# sch.net
KiCad netlist of a schematic drawn in EAGLE
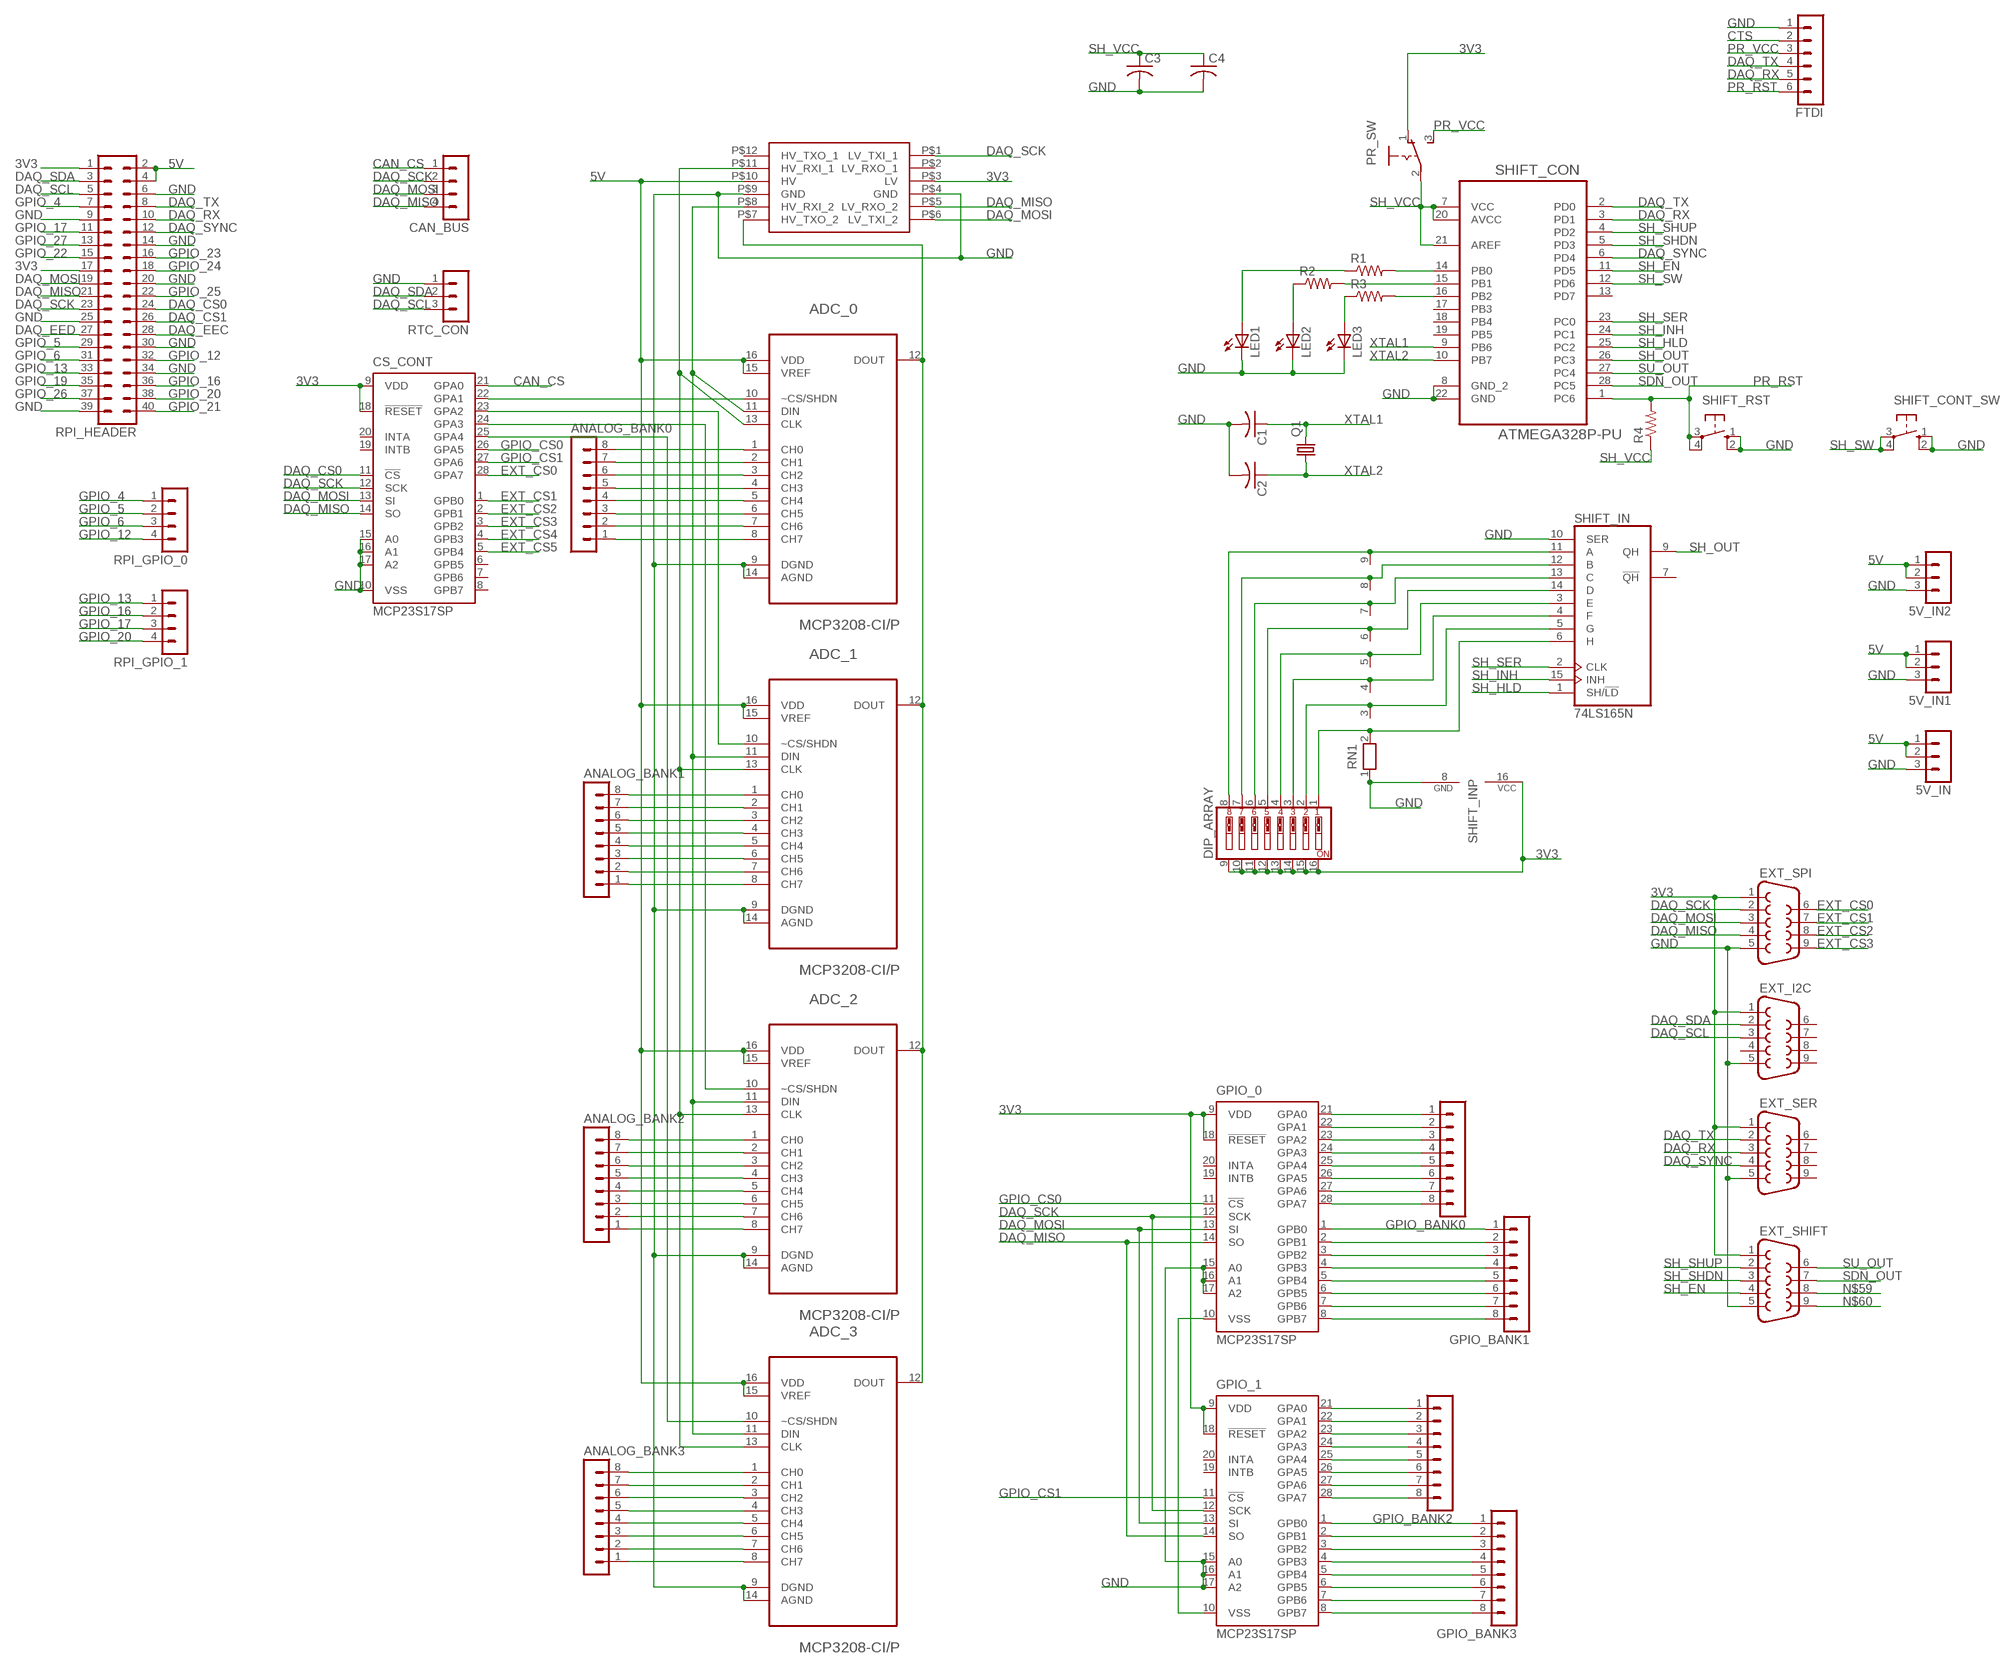
[diagram p0: schematic, sheet 1]

(export (version "E")
  (design (tool "Eeschema 10.0.6"))
  (components
    (comp (ref "5V_IN")
      (value "MA03-1")
      (footprint "eagle-import:MA03-1")
      (libsource (lib "eagle-import") (part "MA03-1"))
    )
    (comp (ref "5V_IN1")
      (value "MA03-1")
      (footprint "eagle-import:MA03-1")
      (libsource (lib "eagle-import") (part "MA03-1"))
    )
    (comp (ref "5V_IN2")
      (value "MA03-1")
      (footprint "eagle-import:MA03-1")
      (libsource (lib "eagle-import") (part "MA03-1"))
    )
    (comp (ref "ADC_0")
      (value "MCP3208-CI/P")
      (footprint "eagle-import:DIP254P762X432-16")
      (libsource (lib "eagle-import") (part "MCP3208-CI/P"))
    )
    (comp (ref "ADC_1")
      (value "MCP3208-CI/P")
      (footprint "eagle-import:DIP254P762X432-16")
      (libsource (lib "eagle-import") (part "MCP3208-CI/P"))
    )
    (comp (ref "ADC_2")
      (value "MCP3208-CI/P")
      (footprint "eagle-import:DIP254P762X432-16")
      (libsource (lib "eagle-import") (part "MCP3208-CI/P"))
    )
    (comp (ref "ADC_3")
      (value "MCP3208-CI/P")
      (footprint "eagle-import:DIP254P762X432-16")
      (libsource (lib "eagle-import") (part "MCP3208-CI/P"))
    )
    (comp (ref "ANALOG_BANK0")
      (value "MA08-1")
      (footprint "eagle-import:MA08-1")
      (libsource (lib "eagle-import") (part "MA08-1"))
    )
    (comp (ref "ANALOG_BANK1")
      (value "MA08-1")
      (footprint "eagle-import:MA08-1")
      (libsource (lib "eagle-import") (part "MA08-1"))
    )
    (comp (ref "ANALOG_BANK2")
      (value "MA08-1")
      (footprint "eagle-import:MA08-1")
      (libsource (lib "eagle-import") (part "MA08-1"))
    )
    (comp (ref "ANALOG_BANK3")
      (value "MA08-1")
      (footprint "eagle-import:MA08-1")
      (libsource (lib "eagle-import") (part "MA08-1"))
    )
    (comp (ref "C1")
      (value "C-US025-025X050")
      (footprint "eagle-import:C025-025X050")
      (libsource (lib "eagle-import") (part "C-US025-025X050"))
    )
    (comp (ref "C2")
      (value "C-US025-025X050")
      (footprint "eagle-import:C025-025X050")
      (libsource (lib "eagle-import") (part "C-US025-025X050"))
    )
    (comp (ref "C3")
      (value "C-US025-025X050")
      (footprint "eagle-import:C025-025X050")
      (libsource (lib "eagle-import") (part "C-US025-025X050"))
    )
    (comp (ref "C4")
      (value "C-US025-025X050")
      (footprint "eagle-import:C025-025X050")
      (libsource (lib "eagle-import") (part "C-US025-025X050"))
    )
    (comp (ref "CAN_BUS")
      (value "MA04-1")
      (footprint "eagle-import:MA04-1")
      (libsource (lib "eagle-import") (part "MA04-1"))
    )
    (comp (ref "CS_CONT")
      (value "MCP23S17SP")
      (footprint "eagle-import:DIL28-3")
      (fields (field (name "MF") "MICROCHIP") (field (name "MPN") "MCP23S17-E/SP"))
      (libsource (lib "eagle-import") (part "MCP23S17SP"))
    )
    (comp (ref "DIP_ARRAY")
      (value "SW_DIP-8")
      (footprint "eagle-import:DIPSWITCH-08")
      (libsource (lib "eagle-import") (part "SW_DIP-8"))
    )
    (comp (ref "EXT_I2C")
      (value "F09VB")
      (footprint "eagle-import:F09VB")
      (libsource (lib "eagle-import") (part "F09VB"))
    )
    (comp (ref "EXT_SER")
      (value "F09VB")
      (footprint "eagle-import:F09VB")
      (libsource (lib "eagle-import") (part "F09VB"))
    )
    (comp (ref "EXT_SHIFT")
      (value "F09VB")
      (footprint "eagle-import:F09VB")
      (libsource (lib "eagle-import") (part "F09VB"))
    )
    (comp (ref "EXT_SPI")
      (value "F09VB")
      (footprint "eagle-import:F09VB")
      (libsource (lib "eagle-import") (part "F09VB"))
    )
    (comp (ref "FTDI")
      (value "MA06-1")
      (footprint "eagle-import:MA06-1")
      (libsource (lib "eagle-import") (part "MA06-1"))
    )
    (comp (ref "GPIO_0")
      (value "MCP23S17SP")
      (footprint "eagle-import:DIL28-3")
      (fields (field (name "MF") "MICROCHIP") (field (name "MPN") "MCP23S17-E/SP"))
      (libsource (lib "eagle-import") (part "MCP23S17SP"))
    )
    (comp (ref "GPIO_1")
      (value "MCP23S17SP")
      (footprint "eagle-import:DIL28-3")
      (fields (field (name "MF") "MICROCHIP") (field (name "MPN") "MCP23S17-E/SP"))
      (libsource (lib "eagle-import") (part "MCP23S17SP"))
    )
    (comp (ref "GPIO_BANK0")
      (value "MA08-1")
      (footprint "eagle-import:MA08-1")
      (libsource (lib "eagle-import") (part "MA08-1"))
    )
    (comp (ref "GPIO_BANK1")
      (value "MA08-1")
      (footprint "eagle-import:MA08-1")
      (libsource (lib "eagle-import") (part "MA08-1"))
    )
    (comp (ref "GPIO_BANK2")
      (value "MA08-1")
      (footprint "eagle-import:MA08-1")
      (libsource (lib "eagle-import") (part "MA08-1"))
    )
    (comp (ref "GPIO_BANK3")
      (value "MA08-1")
      (footprint "eagle-import:MA08-1")
      (libsource (lib "eagle-import") (part "MA08-1"))
    )
    (comp (ref "LED1")
      (value "LED3MM")
      (footprint "eagle-import:LED3MM")
      (libsource (lib "eagle-import") (part "LED3MM"))
    )
    (comp (ref "LED2")
      (value "LED3MM")
      (footprint "eagle-import:LED3MM")
      (libsource (lib "eagle-import") (part "LED3MM"))
    )
    (comp (ref "LED3")
      (value "LED3MM")
      (footprint "eagle-import:LED3MM")
      (libsource (lib "eagle-import") (part "LED3MM"))
    )
    (comp (ref "LOGIC_SHIFT")
      (value "LOGIC_LEVEL_CONVERTER")
      (footprint "eagle-import:LOGIC_LEVEL_CONVERTER")
      (libsource (lib "eagle-import") (part "LOGIC_LEVEL_CONVERTER"))
    )
    (comp (ref "PR_SW")
      (value "255SB")
      (footprint "eagle-import:255SB")
      (libsource (lib "eagle-import") (part "255SB"))
    )
    (comp (ref "Q1")
      (value "CRYSTALHC49S")
      (footprint "eagle-import:HC49_S")
      (libsource (lib "eagle-import") (part "CRYSTALHC49S"))
    )
    (comp (ref "R1")
      (value "R-US_0204/5")
      (footprint "eagle-import:0204_5")
      (libsource (lib "eagle-import") (part "R-US_0204/5"))
    )
    (comp (ref "R2")
      (value "R-US_0204/5")
      (footprint "eagle-import:0204_5")
      (libsource (lib "eagle-import") (part "R-US_0204/5"))
    )
    (comp (ref "R3")
      (value "R-US_0204/5")
      (footprint "eagle-import:0204_5")
      (libsource (lib "eagle-import") (part "R-US_0204/5"))
    )
    (comp (ref "R4")
      (value "R-US_0204/5")
      (footprint "eagle-import:0204_5")
      (libsource (lib "eagle-import") (part "R-US_0204/5"))
    )
    (comp (ref "RN1")
      (value "RN08")
      (footprint "eagle-import:RN-9")
      (libsource (lib "eagle-import") (part "RN08"))
    )
    (comp (ref "RPI_GPIO_0")
      (value "MA04-1")
      (footprint "eagle-import:MA04-1")
      (libsource (lib "eagle-import") (part "MA04-1"))
    )
    (comp (ref "RPI_GPIO_1")
      (value "MA04-1")
      (footprint "eagle-import:MA04-1")
      (libsource (lib "eagle-import") (part "MA04-1"))
    )
    (comp (ref "RPI_HEADER")
      (value "MA20-2")
      (footprint "eagle-import:MA20-2")
      (libsource (lib "eagle-import") (part "MA20-2"))
    )
    (comp (ref "RTC_CON")
      (value "MA03-1")
      (footprint "eagle-import:MA03-1")
      (libsource (lib "eagle-import") (part "MA03-1"))
    )
    (comp (ref "SHIFT_CON")
      (value "ATMEGA328P-PU")
      (footprint "eagle-import:DIP254P762X457-28")
      (libsource (lib "eagle-import") (part "ATMEGA328P-PU"))
    )
    (comp (ref "SHIFT_CONT_SW")
      (value "10-XX")
      (footprint "eagle-import:B3F-10XX")
      (fields (field (name "MPN") "B3F-1000"))
      (libsource (lib "eagle-import") (part "10-XX"))
    )
    (comp (ref "SHIFT_IN")
      (value "74LS165N")
      (footprint "eagle-import:DIL16")
      (libsource (lib "eagle-import") (part "74165NLS"))
    )
    (comp (ref "SHIFT_RST")
      (value "10-XX")
      (footprint "eagle-import:B3F-10XX")
      (fields (field (name "MPN") "B3F-1000"))
      (libsource (lib "eagle-import") (part "10-XX"))
    )
  )
  (nets
    (net (code "1") (name "/3V3") (class "Default")
      (node (ref "CS_CONT") (pin "18") (pinfunction "~{RESET}_18") (pintype "input"))
      (node (ref "CS_CONT") (pin "9") (pinfunction "VDD_9") (pintype "power_in"))
      (node (ref "DIP_ARRAY") (pin "10") (pinfunction "10_10") (pintype "passive"))
      (node (ref "DIP_ARRAY") (pin "11") (pinfunction "11_11") (pintype "passive"))
      (node (ref "DIP_ARRAY") (pin "12") (pinfunction "12_12") (pintype "passive"))
      (node (ref "DIP_ARRAY") (pin "13") (pinfunction "13_13") (pintype "passive"))
      (node (ref "DIP_ARRAY") (pin "14") (pinfunction "14_14") (pintype "passive"))
      (node (ref "DIP_ARRAY") (pin "15") (pinfunction "15_15") (pintype "passive"))
      (node (ref "DIP_ARRAY") (pin "16") (pinfunction "16_16") (pintype "passive"))
      (node (ref "DIP_ARRAY") (pin "9") (pinfunction "9_9") (pintype "passive"))
      (node (ref "EXT_I2C") (pin "1") (pinfunction "1_1") (pintype "passive"))
      (node (ref "EXT_SER") (pin "1") (pinfunction "1_1") (pintype "passive"))
      (node (ref "EXT_SHIFT") (pin "1") (pinfunction "1_1") (pintype "passive"))
      (node (ref "EXT_SPI") (pin "1") (pinfunction "1_1") (pintype "passive"))
      (node (ref "GPIO_0") (pin "18") (pinfunction "~{RESET}_18") (pintype "input"))
      (node (ref "GPIO_0") (pin "9") (pinfunction "VDD_9") (pintype "power_in"))
      (node (ref "GPIO_1") (pin "18") (pinfunction "~{RESET}_18") (pintype "input"))
      (node (ref "GPIO_1") (pin "9") (pinfunction "VDD_9") (pintype "power_in"))
      (node (ref "LOGIC_SHIFT") (pin "P$3") (pinfunction "LV_P$3") (pintype "bidirectional"))
      (node (ref "PR_SW") (pin "1") (pinfunction "O_1") (pintype "passive"))
      (node (ref "RPI_HEADER") (pin "1") (pinfunction "1_1") (pintype "passive"))
      (node (ref "RPI_HEADER") (pin "17") (pinfunction "17_17") (pintype "passive"))
      (node (ref "SHIFT_IN") (pin "16") (pinfunction "VCC_16") (pintype "power_in"))
    )
    (net (code "2") (name "/5V") (class "Default")
      (node (ref "5V_IN") (pin "1") (pinfunction "1_1") (pintype "passive"))
      (node (ref "5V_IN") (pin "2") (pinfunction "2_2") (pintype "passive"))
      (node (ref "5V_IN1") (pin "1") (pinfunction "1_1") (pintype "passive"))
      (node (ref "5V_IN1") (pin "2") (pinfunction "2_2") (pintype "passive"))
      (node (ref "5V_IN2") (pin "1") (pinfunction "1_1") (pintype "passive"))
      (node (ref "5V_IN2") (pin "2") (pinfunction "2_2") (pintype "passive"))
      (node (ref "ADC_0") (pin "15") (pinfunction "VREF_15") (pintype "power_in"))
      (node (ref "ADC_0") (pin "16") (pinfunction "VDD_16") (pintype "power_in"))
      (node (ref "ADC_1") (pin "15") (pinfunction "VREF_15") (pintype "power_in"))
      (node (ref "ADC_1") (pin "16") (pinfunction "VDD_16") (pintype "power_in"))
      (node (ref "ADC_2") (pin "15") (pinfunction "VREF_15") (pintype "power_in"))
      (node (ref "ADC_2") (pin "16") (pinfunction "VDD_16") (pintype "power_in"))
      (node (ref "ADC_3") (pin "15") (pinfunction "VREF_15") (pintype "power_in"))
      (node (ref "ADC_3") (pin "16") (pinfunction "VDD_16") (pintype "power_in"))
      (node (ref "LOGIC_SHIFT") (pin "P$10") (pinfunction "HV_P$10") (pintype "bidirectional"))
      (node (ref "RPI_HEADER") (pin "2") (pinfunction "2_2") (pintype "passive"))
      (node (ref "RPI_HEADER") (pin "4") (pinfunction "4_4") (pintype "passive"))
    )
    (net (code "3") (name "/CAN_CS") (class "Default")
      (node (ref "CAN_BUS") (pin "1") (pinfunction "1_1") (pintype "passive"))
      (node (ref "CS_CONT") (pin "21") (pinfunction "GPA0_21") (pintype "bidirectional"))
    )
    (net (code "4") (name "/CTS") (class "Default")
      (node (ref "FTDI") (pin "2") (pinfunction "2_2") (pintype "passive"))
    )
    (net (code "5") (name "/DAQ_CS0") (class "Default")
      (node (ref "CS_CONT") (pin "11") (pinfunction "~{CS}_11") (pintype "input"))
      (node (ref "RPI_HEADER") (pin "24") (pinfunction "24_24") (pintype "passive"))
    )
    (net (code "6") (name "/DAQ_CS1") (class "Default")
      (node (ref "RPI_HEADER") (pin "26") (pinfunction "26_26") (pintype "passive"))
    )
    (net (code "7") (name "/DAQ_EEC") (class "Default")
      (node (ref "RPI_HEADER") (pin "28") (pinfunction "28_28") (pintype "passive"))
    )
    (net (code "8") (name "/DAQ_EED") (class "Default")
      (node (ref "RPI_HEADER") (pin "27") (pinfunction "27_27") (pintype "passive"))
    )
    (net (code "9") (name "/DAQ_MISO") (class "Default")
      (node (ref "CAN_BUS") (pin "4") (pinfunction "4_4") (pintype "passive"))
      (node (ref "CS_CONT") (pin "14") (pinfunction "SO_14") (pintype "output"))
      (node (ref "EXT_SPI") (pin "4") (pinfunction "4_4") (pintype "passive"))
      (node (ref "GPIO_0") (pin "14") (pinfunction "SO_14") (pintype "output"))
      (node (ref "GPIO_1") (pin "14") (pinfunction "SO_14") (pintype "output"))
      (node (ref "LOGIC_SHIFT") (pin "P$5") (pinfunction "LV_RXO_2_P$5") (pintype "bidirectional"))
      (node (ref "RPI_HEADER") (pin "21") (pinfunction "21_21") (pintype "passive"))
    )
    (net (code "10") (name "/DAQ_MOSI") (class "Default")
      (node (ref "CAN_BUS") (pin "3") (pinfunction "3_3") (pintype "passive"))
      (node (ref "CS_CONT") (pin "13") (pinfunction "SI_13") (pintype "input"))
      (node (ref "EXT_SPI") (pin "3") (pinfunction "3_3") (pintype "passive"))
      (node (ref "GPIO_0") (pin "13") (pinfunction "SI_13") (pintype "input"))
      (node (ref "GPIO_1") (pin "13") (pinfunction "SI_13") (pintype "input"))
      (node (ref "LOGIC_SHIFT") (pin "P$6") (pinfunction "LV_TXI_2_P$6") (pintype "bidirectional"))
      (node (ref "RPI_HEADER") (pin "19") (pinfunction "19_19") (pintype "passive"))
    )
    (net (code "11") (name "/DAQ_RX") (class "Default")
      (node (ref "EXT_SER") (pin "3") (pinfunction "3_3") (pintype "passive"))
      (node (ref "FTDI") (pin "5") (pinfunction "5_5") (pintype "passive"))
      (node (ref "RPI_HEADER") (pin "10") (pinfunction "10_10") (pintype "passive"))
      (node (ref "SHIFT_CON") (pin "3") (pinfunction "PD1_3") (pintype "bidirectional"))
    )
    (net (code "12") (name "/DAQ_SCK") (class "Default")
      (node (ref "CAN_BUS") (pin "2") (pinfunction "2_2") (pintype "passive"))
      (node (ref "CS_CONT") (pin "12") (pinfunction "SCK_12") (pintype "input"))
      (node (ref "EXT_SPI") (pin "2") (pinfunction "2_2") (pintype "passive"))
      (node (ref "GPIO_0") (pin "12") (pinfunction "SCK_12") (pintype "input"))
      (node (ref "GPIO_1") (pin "12") (pinfunction "SCK_12") (pintype "input"))
      (node (ref "LOGIC_SHIFT") (pin "P$1") (pinfunction "LV_TXI_1_P$1") (pintype "bidirectional"))
      (node (ref "RPI_HEADER") (pin "23") (pinfunction "23_23") (pintype "passive"))
    )
    (net (code "13") (name "/DAQ_SCL") (class "Default")
      (node (ref "EXT_I2C") (pin "3") (pinfunction "3_3") (pintype "passive"))
      (node (ref "RPI_HEADER") (pin "5") (pinfunction "5_5") (pintype "passive"))
      (node (ref "RTC_CON") (pin "3") (pinfunction "3_3") (pintype "passive"))
    )
    (net (code "14") (name "/DAQ_SDA") (class "Default")
      (node (ref "EXT_I2C") (pin "2") (pinfunction "2_2") (pintype "passive"))
      (node (ref "RPI_HEADER") (pin "3") (pinfunction "3_3") (pintype "passive"))
      (node (ref "RTC_CON") (pin "2") (pinfunction "2_2") (pintype "passive"))
    )
    (net (code "15") (name "/DAQ_SYNC") (class "Default")
      (node (ref "EXT_SER") (pin "4") (pinfunction "4_4") (pintype "passive"))
      (node (ref "RPI_HEADER") (pin "12") (pinfunction "12_12") (pintype "passive"))
      (node (ref "SHIFT_CON") (pin "6") (pinfunction "PD4_6") (pintype "bidirectional"))
    )
    (net (code "16") (name "/DAQ_TX") (class "Default")
      (node (ref "EXT_SER") (pin "2") (pinfunction "2_2") (pintype "passive"))
      (node (ref "FTDI") (pin "4") (pinfunction "4_4") (pintype "passive"))
      (node (ref "RPI_HEADER") (pin "8") (pinfunction "8_8") (pintype "passive"))
      (node (ref "SHIFT_CON") (pin "2") (pinfunction "PD0_2") (pintype "bidirectional"))
    )
    (net (code "17") (name "/EXT_CS0") (class "Default")
      (node (ref "CS_CONT") (pin "28") (pinfunction "GPA7_28") (pintype "bidirectional"))
      (node (ref "EXT_SPI") (pin "6") (pinfunction "6_6") (pintype "passive"))
    )
    (net (code "18") (name "/EXT_CS1") (class "Default")
      (node (ref "CS_CONT") (pin "1") (pinfunction "GPB0_1") (pintype "bidirectional"))
      (node (ref "EXT_SPI") (pin "7") (pinfunction "7_7") (pintype "passive"))
    )
    (net (code "19") (name "/EXT_CS2") (class "Default")
      (node (ref "CS_CONT") (pin "2") (pinfunction "GPB1_2") (pintype "bidirectional"))
      (node (ref "EXT_SPI") (pin "8") (pinfunction "8_8") (pintype "passive"))
    )
    (net (code "20") (name "/EXT_CS3") (class "Default")
      (node (ref "CS_CONT") (pin "3") (pinfunction "GPB2_3") (pintype "bidirectional"))
      (node (ref "EXT_SPI") (pin "9") (pinfunction "9_9") (pintype "passive"))
    )
    (net (code "21") (name "/EXT_CS4") (class "Default")
      (node (ref "CS_CONT") (pin "4") (pinfunction "GPB3_4") (pintype "bidirectional"))
    )
    (net (code "22") (name "/EXT_CS5") (class "Default")
      (node (ref "CS_CONT") (pin "5") (pinfunction "GPB4_5") (pintype "bidirectional"))
    )
    (net (code "23") (name "/GND") (class "Default")
      (node (ref "5V_IN") (pin "3") (pinfunction "3_3") (pintype "passive"))
      (node (ref "5V_IN1") (pin "3") (pinfunction "3_3") (pintype "passive"))
      (node (ref "5V_IN2") (pin "3") (pinfunction "3_3") (pintype "passive"))
      (node (ref "ADC_0") (pin "14") (pinfunction "AGND_14") (pintype "passive"))
      (node (ref "ADC_0") (pin "9") (pinfunction "DGND_9") (pintype "passive"))
      (node (ref "ADC_1") (pin "14") (pinfunction "AGND_14") (pintype "passive"))
      (node (ref "ADC_1") (pin "9") (pinfunction "DGND_9") (pintype "passive"))
      (node (ref "ADC_2") (pin "14") (pinfunction "AGND_14") (pintype "passive"))
      (node (ref "ADC_2") (pin "9") (pinfunction "DGND_9") (pintype "passive"))
      (node (ref "ADC_3") (pin "14") (pinfunction "AGND_14") (pintype "passive"))
      (node (ref "ADC_3") (pin "9") (pinfunction "DGND_9") (pintype "passive"))
      (node (ref "C1") (pin "2") (pinfunction "2_2") (pintype "passive"))
      (node (ref "C2") (pin "2") (pinfunction "2_2") (pintype "passive"))
      (node (ref "C3") (pin "2") (pinfunction "2_2") (pintype "passive"))
      (node (ref "C4") (pin "2") (pinfunction "2_2") (pintype "passive"))
      (node (ref "CS_CONT") (pin "10") (pinfunction "VSS_10") (pintype "power_in"))
      (node (ref "CS_CONT") (pin "15") (pinfunction "A0_15") (pintype "input"))
      (node (ref "CS_CONT") (pin "16") (pinfunction "A1_16") (pintype "input"))
      (node (ref "CS_CONT") (pin "17") (pinfunction "A2_17") (pintype "input"))
      (node (ref "EXT_I2C") (pin "5") (pinfunction "5_5") (pintype "passive"))
      (node (ref "EXT_SER") (pin "5") (pinfunction "5_5") (pintype "passive"))
      (node (ref "EXT_SHIFT") (pin "5") (pinfunction "5_5") (pintype "passive"))
      (node (ref "EXT_SPI") (pin "5") (pinfunction "5_5") (pintype "passive"))
      (node (ref "FTDI") (pin "1") (pinfunction "1_1") (pintype "passive"))
      (node (ref "GPIO_0") (pin "15") (pinfunction "A0_15") (pintype "input"))
      (node (ref "GPIO_0") (pin "16") (pinfunction "A1_16") (pintype "input"))
      (node (ref "GPIO_0") (pin "17") (pinfunction "A2_17") (pintype "input"))
      (node (ref "GPIO_1") (pin "15") (pinfunction "A0_15") (pintype "input"))
      (node (ref "GPIO_1") (pin "16") (pinfunction "A1_16") (pintype "input"))
      (node (ref "GPIO_1") (pin "17") (pinfunction "A2_17") (pintype "input"))
      (node (ref "LED1") (pin "K") (pinfunction "C_K") (pintype "passive"))
      (node (ref "LED2") (pin "K") (pinfunction "C_K") (pintype "passive"))
      (node (ref "LED3") (pin "K") (pinfunction "C_K") (pintype "passive"))
      (node (ref "LOGIC_SHIFT") (pin "P$4") (pinfunction "GND_P$4") (pintype "bidirectional"))
      (node (ref "LOGIC_SHIFT") (pin "P$9") (pinfunction "GND_P$9") (pintype "bidirectional"))
      (node (ref "RN1") (pin "1") (pinfunction "1_1") (pintype "passive"))
      (node (ref "RPI_HEADER") (pin "14") (pinfunction "14_14") (pintype "passive"))
      (node (ref "RPI_HEADER") (pin "20") (pinfunction "20_20") (pintype "passive"))
      (node (ref "RPI_HEADER") (pin "25") (pinfunction "25_25") (pintype "passive"))
      (node (ref "RPI_HEADER") (pin "30") (pinfunction "30_30") (pintype "passive"))
      (node (ref "RPI_HEADER") (pin "34") (pinfunction "34_34") (pintype "passive"))
      (node (ref "RPI_HEADER") (pin "39") (pinfunction "39_39") (pintype "passive"))
      (node (ref "RPI_HEADER") (pin "6") (pinfunction "6_6") (pintype "passive"))
      (node (ref "RPI_HEADER") (pin "9") (pinfunction "9_9") (pintype "passive"))
      (node (ref "RTC_CON") (pin "1") (pinfunction "1_1") (pintype "passive"))
      (node (ref "SHIFT_CON") (pin "22") (pinfunction "GND_22") (pintype "passive"))
      (node (ref "SHIFT_CON") (pin "8") (pinfunction "GND_2_8") (pintype "passive"))
      (node (ref "SHIFT_CONT_SW") (pin "1") (pinfunction "S_1") (pintype "passive"))
      (node (ref "SHIFT_CONT_SW") (pin "2") (pinfunction "S1_2") (pintype "passive"))
      (node (ref "SHIFT_IN") (pin "10") (pinfunction "SER_10") (pintype "input"))
      (node (ref "SHIFT_IN") (pin "8") (pinfunction "GND_8") (pintype "power_in"))
      (node (ref "SHIFT_RST") (pin "1") (pinfunction "S_1") (pintype "passive"))
      (node (ref "SHIFT_RST") (pin "2") (pinfunction "S1_2") (pintype "passive"))
    )
    (net (code "24") (name "/GPIO_4") (class "Default")
      (node (ref "RPI_GPIO_0") (pin "1") (pinfunction "1_1") (pintype "passive"))
      (node (ref "RPI_HEADER") (pin "7") (pinfunction "7_7") (pintype "passive"))
    )
    (net (code "25") (name "/GPIO_5") (class "Default")
      (node (ref "RPI_GPIO_0") (pin "2") (pinfunction "2_2") (pintype "passive"))
      (node (ref "RPI_HEADER") (pin "29") (pinfunction "29_29") (pintype "passive"))
    )
    (net (code "26") (name "/GPIO_6") (class "Default")
      (node (ref "RPI_GPIO_0") (pin "3") (pinfunction "3_3") (pintype "passive"))
      (node (ref "RPI_HEADER") (pin "31") (pinfunction "31_31") (pintype "passive"))
    )
    (net (code "27") (name "/GPIO_12") (class "Default")
      (node (ref "RPI_GPIO_0") (pin "4") (pinfunction "4_4") (pintype "passive"))
      (node (ref "RPI_HEADER") (pin "32") (pinfunction "32_32") (pintype "passive"))
    )
    (net (code "28") (name "/GPIO_13") (class "Default")
      (node (ref "RPI_GPIO_1") (pin "1") (pinfunction "1_1") (pintype "passive"))
      (node (ref "RPI_HEADER") (pin "33") (pinfunction "33_33") (pintype "passive"))
    )
    (net (code "29") (name "/GPIO_16") (class "Default")
      (node (ref "RPI_GPIO_1") (pin "2") (pinfunction "2_2") (pintype "passive"))
      (node (ref "RPI_HEADER") (pin "36") (pinfunction "36_36") (pintype "passive"))
    )
    (net (code "30") (name "/GPIO_17") (class "Default")
      (node (ref "RPI_GPIO_1") (pin "3") (pinfunction "3_3") (pintype "passive"))
      (node (ref "RPI_HEADER") (pin "11") (pinfunction "11_11") (pintype "passive"))
    )
    (net (code "31") (name "/GPIO_19") (class "Default")
      (node (ref "RPI_HEADER") (pin "35") (pinfunction "35_35") (pintype "passive"))
    )
    (net (code "32") (name "/GPIO_20") (class "Default")
      (node (ref "RPI_GPIO_1") (pin "4") (pinfunction "4_4") (pintype "passive"))
      (node (ref "RPI_HEADER") (pin "38") (pinfunction "38_38") (pintype "passive"))
    )
    (net (code "33") (name "/GPIO_21") (class "Default")
      (node (ref "RPI_HEADER") (pin "40") (pinfunction "40_40") (pintype "passive"))
    )
    (net (code "34") (name "/GPIO_22") (class "Default")
      (node (ref "RPI_HEADER") (pin "15") (pinfunction "15_15") (pintype "passive"))
    )
    (net (code "35") (name "/GPIO_23") (class "Default")
      (node (ref "RPI_HEADER") (pin "16") (pinfunction "16_16") (pintype "passive"))
    )
    (net (code "36") (name "/GPIO_24") (class "Default")
      (node (ref "RPI_HEADER") (pin "18") (pinfunction "18_18") (pintype "passive"))
    )
    (net (code "37") (name "/GPIO_25") (class "Default")
      (node (ref "RPI_HEADER") (pin "22") (pinfunction "22_22") (pintype "passive"))
    )
    (net (code "38") (name "/GPIO_26") (class "Default")
      (node (ref "RPI_HEADER") (pin "37") (pinfunction "37_37") (pintype "passive"))
    )
    (net (code "39") (name "/GPIO_27") (class "Default")
      (node (ref "RPI_HEADER") (pin "13") (pinfunction "13_13") (pintype "passive"))
    )
    (net (code "40") (name "/GPIO_CS0") (class "Default")
      (node (ref "CS_CONT") (pin "26") (pinfunction "GPA5_26") (pintype "bidirectional"))
      (node (ref "GPIO_0") (pin "11") (pinfunction "~{CS}_11") (pintype "input"))
    )
    (net (code "41") (name "/GPIO_CS1") (class "Default")
      (node (ref "CS_CONT") (pin "27") (pinfunction "GPA6_27") (pintype "bidirectional"))
      (node (ref "GPIO_1") (pin "11") (pinfunction "~{CS}_11") (pintype "input"))
    )
    (net (code "42") (name "/N$59") (class "Default")
      (node (ref "EXT_SHIFT") (pin "8") (pinfunction "8_8") (pintype "passive"))
    )
    (net (code "43") (name "/N$60") (class "Default")
      (node (ref "EXT_SHIFT") (pin "9") (pinfunction "9_9") (pintype "passive"))
    )
    (net (code "44") (name "/PR_RST") (class "Default")
      (node (ref "FTDI") (pin "6") (pinfunction "6_6") (pintype "passive"))
      (node (ref "R4") (pin "2") (pinfunction "2_2") (pintype "passive"))
      (node (ref "SHIFT_CON") (pin "1") (pinfunction "PC6_1") (pintype "bidirectional"))
      (node (ref "SHIFT_RST") (pin "3") (pinfunction "P_3") (pintype "passive"))
      (node (ref "SHIFT_RST") (pin "4") (pinfunction "P1_4") (pintype "passive"))
    )
    (net (code "45") (name "/PR_VCC") (class "Default")
      (node (ref "FTDI") (pin "3") (pinfunction "3_3") (pintype "passive"))
      (node (ref "PR_SW") (pin "3") (pinfunction "S_3") (pintype "passive"))
    )
    (net (code "46") (name "/SDN_OUT") (class "Default")
      (node (ref "EXT_SHIFT") (pin "7") (pinfunction "7_7") (pintype "passive"))
      (node (ref "SHIFT_CON") (pin "28") (pinfunction "PC5_28") (pintype "bidirectional"))
    )
    (net (code "47") (name "/SH_EN") (class "Default")
      (node (ref "EXT_SHIFT") (pin "4") (pinfunction "4_4") (pintype "passive"))
      (node (ref "SHIFT_CON") (pin "11") (pinfunction "PD5_11") (pintype "bidirectional"))
    )
    (net (code "48") (name "/SH_HLD") (class "Default")
      (node (ref "SHIFT_CON") (pin "25") (pinfunction "PC2_25") (pintype "bidirectional"))
      (node (ref "SHIFT_IN") (pin "1") (pinfunction "SH/~{LD}_1") (pintype "input"))
    )
    (net (code "49") (name "/SH_INH") (class "Default")
      (node (ref "SHIFT_CON") (pin "24") (pinfunction "PC1_24") (pintype "bidirectional"))
      (node (ref "SHIFT_IN") (pin "15") (pinfunction "INH_15") (pintype "input"))
    )
    (net (code "50") (name "/SH_OUT") (class "Default")
      (node (ref "SHIFT_CON") (pin "26") (pinfunction "PC3_26") (pintype "bidirectional"))
      (node (ref "SHIFT_IN") (pin "9") (pinfunction "QH_9") (pintype "output"))
    )
    (net (code "51") (name "/SH_SER") (class "Default")
      (node (ref "SHIFT_CON") (pin "23") (pinfunction "PC0_23") (pintype "bidirectional"))
      (node (ref "SHIFT_IN") (pin "2") (pinfunction "CLK_2") (pintype "input"))
    )
    (net (code "52") (name "/SH_SHDN") (class "Default")
      (node (ref "EXT_SHIFT") (pin "3") (pinfunction "3_3") (pintype "passive"))
      (node (ref "SHIFT_CON") (pin "5") (pinfunction "PD3_5") (pintype "bidirectional"))
    )
    (net (code "53") (name "/SH_SHUP") (class "Default")
      (node (ref "EXT_SHIFT") (pin "2") (pinfunction "2_2") (pintype "passive"))
      (node (ref "SHIFT_CON") (pin "4") (pinfunction "PD2_4") (pintype "bidirectional"))
    )
    (net (code "54") (name "/SH_SW") (class "Default")
      (node (ref "SHIFT_CON") (pin "12") (pinfunction "PD6_12") (pintype "bidirectional"))
      (node (ref "SHIFT_CONT_SW") (pin "3") (pinfunction "P_3") (pintype "passive"))
      (node (ref "SHIFT_CONT_SW") (pin "4") (pinfunction "P1_4") (pintype "passive"))
    )
    (net (code "55") (name "/SH_VCC") (class "Default")
      (node (ref "C3") (pin "1") (pinfunction "1_1") (pintype "passive"))
      (node (ref "C4") (pin "1") (pinfunction "1_1") (pintype "passive"))
      (node (ref "PR_SW") (pin "2") (pinfunction "P_2") (pintype "passive"))
      (node (ref "R4") (pin "1") (pinfunction "1_1") (pintype "passive"))
      (node (ref "SHIFT_CON") (pin "20") (pinfunction "AVCC_20") (pintype "power_in"))
      (node (ref "SHIFT_CON") (pin "21") (pinfunction "AREF_21") (pintype "input"))
      (node (ref "SHIFT_CON") (pin "7") (pinfunction "VCC_7") (pintype "power_in"))
    )
    (net (code "56") (name "/SU_OUT") (class "Default")
      (node (ref "EXT_SHIFT") (pin "6") (pinfunction "6_6") (pintype "passive"))
      (node (ref "SHIFT_CON") (pin "27") (pinfunction "PC4_27") (pintype "bidirectional"))
    )
    (net (code "57") (name "/XTAL1") (class "Default")
      (node (ref "C1") (pin "1") (pinfunction "1_1") (pintype "passive"))
      (node (ref "Q1") (pin "2") (pinfunction "2_2") (pintype "passive"))
      (node (ref "SHIFT_CON") (pin "9") (pinfunction "PB6_9") (pintype "bidirectional"))
    )
    (net (code "58") (name "/XTAL2") (class "Default")
      (node (ref "C2") (pin "1") (pinfunction "1_1") (pintype "passive"))
      (node (ref "Q1") (pin "1") (pinfunction "1_1") (pintype "passive"))
      (node (ref "SHIFT_CON") (pin "10") (pinfunction "PB7_10") (pintype "bidirectional"))
    )
    (net (code "59") (name "Net-(ADC_0-CH0)") (class "Default")
      (node (ref "ADC_0") (pin "1") (pinfunction "CH0_1") (pintype "input"))
      (node (ref "ANALOG_BANK0") (pin "8") (pinfunction "8_8") (pintype "passive"))
    )
    (net (code "60") (name "Net-(ADC_0-CH1)") (class "Default")
      (node (ref "ADC_0") (pin "2") (pinfunction "CH1_2") (pintype "input"))
      (node (ref "ANALOG_BANK0") (pin "7") (pinfunction "7_7") (pintype "passive"))
    )
    (net (code "61") (name "Net-(ADC_0-CH2)") (class "Default")
      (node (ref "ADC_0") (pin "3") (pinfunction "CH2_3") (pintype "input"))
      (node (ref "ANALOG_BANK0") (pin "6") (pinfunction "6_6") (pintype "passive"))
    )
    (net (code "62") (name "Net-(ADC_0-CH3)") (class "Default")
      (node (ref "ADC_0") (pin "4") (pinfunction "CH3_4") (pintype "input"))
      (node (ref "ANALOG_BANK0") (pin "5") (pinfunction "5_5") (pintype "passive"))
    )
    (net (code "63") (name "Net-(ADC_0-CH4)") (class "Default")
      (node (ref "ADC_0") (pin "5") (pinfunction "CH4_5") (pintype "input"))
      (node (ref "ANALOG_BANK0") (pin "4") (pinfunction "4_4") (pintype "passive"))
    )
    (net (code "64") (name "Net-(ADC_0-CH5)") (class "Default")
      (node (ref "ADC_0") (pin "6") (pinfunction "CH5_6") (pintype "input"))
      (node (ref "ANALOG_BANK0") (pin "3") (pinfunction "3_3") (pintype "passive"))
    )
    (net (code "65") (name "Net-(ADC_0-CH6)") (class "Default")
      (node (ref "ADC_0") (pin "7") (pinfunction "CH6_7") (pintype "input"))
      (node (ref "ANALOG_BANK0") (pin "2") (pinfunction "2_2") (pintype "passive"))
    )
    (net (code "66") (name "Net-(ADC_0-CH7)") (class "Default")
      (node (ref "ADC_0") (pin "8") (pinfunction "CH7_8") (pintype "input"))
      (node (ref "ANALOG_BANK0") (pin "1") (pinfunction "1_1") (pintype "passive"))
    )
    (net (code "67") (name "Net-(ADC_0-CLK)") (class "Default")
      (node (ref "ADC_0") (pin "13") (pinfunction "CLK_13") (pintype "input"))
      (node (ref "ADC_1") (pin "13") (pinfunction "CLK_13") (pintype "input"))
      (node (ref "ADC_2") (pin "13") (pinfunction "CLK_13") (pintype "input"))
      (node (ref "ADC_3") (pin "13") (pinfunction "CLK_13") (pintype "input"))
      (node (ref "LOGIC_SHIFT") (pin "P$11") (pinfunction "HV_RXI_1_P$11") (pintype "bidirectional"))
    )
    (net (code "68") (name "Net-(ADC_0-DIN)") (class "Default")
      (node (ref "ADC_0") (pin "11") (pinfunction "DIN_11") (pintype "input"))
      (node (ref "ADC_1") (pin "11") (pinfunction "DIN_11") (pintype "input"))
      (node (ref "ADC_2") (pin "11") (pinfunction "DIN_11") (pintype "input"))
      (node (ref "ADC_3") (pin "11") (pinfunction "DIN_11") (pintype "input"))
      (node (ref "LOGIC_SHIFT") (pin "P$8") (pinfunction "HV_RXI_2_P$8") (pintype "bidirectional"))
    )
    (net (code "69") (name "Net-(ADC_0-DOUT)") (class "Default")
      (node (ref "ADC_0") (pin "12") (pinfunction "DOUT_12") (pintype "output"))
      (node (ref "ADC_1") (pin "12") (pinfunction "DOUT_12") (pintype "output"))
      (node (ref "ADC_2") (pin "12") (pinfunction "DOUT_12") (pintype "output"))
      (node (ref "ADC_3") (pin "12") (pinfunction "DOUT_12") (pintype "output"))
      (node (ref "LOGIC_SHIFT") (pin "P$7") (pinfunction "HV_TXO_2_P$7") (pintype "bidirectional"))
    )
    (net (code "70") (name "Net-(ADC_0-~{CS{slash}SHDN})") (class "Default")
      (node (ref "ADC_0") (pin "10") (pinfunction "~{CS/SHDN}_10") (pintype "input"))
      (node (ref "CS_CONT") (pin "22") (pinfunction "GPA1_22") (pintype "bidirectional"))
    )
    (net (code "71") (name "Net-(ADC_1-CH0)") (class "Default")
      (node (ref "ADC_1") (pin "1") (pinfunction "CH0_1") (pintype "input"))
      (node (ref "ANALOG_BANK1") (pin "8") (pinfunction "8_8") (pintype "passive"))
    )
    (net (code "72") (name "Net-(ADC_1-CH1)") (class "Default")
      (node (ref "ADC_1") (pin "2") (pinfunction "CH1_2") (pintype "input"))
      (node (ref "ANALOG_BANK1") (pin "7") (pinfunction "7_7") (pintype "passive"))
    )
    (net (code "73") (name "Net-(ADC_1-CH2)") (class "Default")
      (node (ref "ADC_1") (pin "3") (pinfunction "CH2_3") (pintype "input"))
      (node (ref "ANALOG_BANK1") (pin "6") (pinfunction "6_6") (pintype "passive"))
    )
    (net (code "74") (name "Net-(ADC_1-CH3)") (class "Default")
      (node (ref "ADC_1") (pin "4") (pinfunction "CH3_4") (pintype "input"))
      (node (ref "ANALOG_BANK1") (pin "5") (pinfunction "5_5") (pintype "passive"))
    )
    (net (code "75") (name "Net-(ADC_1-CH4)") (class "Default")
      (node (ref "ADC_1") (pin "5") (pinfunction "CH4_5") (pintype "input"))
      (node (ref "ANALOG_BANK1") (pin "4") (pinfunction "4_4") (pintype "passive"))
    )
    (net (code "76") (name "Net-(ADC_1-CH5)") (class "Default")
      (node (ref "ADC_1") (pin "6") (pinfunction "CH5_6") (pintype "input"))
      (node (ref "ANALOG_BANK1") (pin "3") (pinfunction "3_3") (pintype "passive"))
    )
    (net (code "77") (name "Net-(ADC_1-CH6)") (class "Default")
      (node (ref "ADC_1") (pin "7") (pinfunction "CH6_7") (pintype "input"))
      (node (ref "ANALOG_BANK1") (pin "2") (pinfunction "2_2") (pintype "passive"))
    )
    (net (code "78") (name "Net-(ADC_1-CH7)") (class "Default")
      (node (ref "ADC_1") (pin "8") (pinfunction "CH7_8") (pintype "input"))
      (node (ref "ANALOG_BANK1") (pin "1") (pinfunction "1_1") (pintype "passive"))
    )
    (net (code "79") (name "Net-(ADC_1-~{CS{slash}SHDN})") (class "Default")
      (node (ref "ADC_1") (pin "10") (pinfunction "~{CS/SHDN}_10") (pintype "input"))
      (node (ref "CS_CONT") (pin "23") (pinfunction "GPA2_23") (pintype "bidirectional"))
    )
    (net (code "80") (name "Net-(ADC_2-CH0)") (class "Default")
      (node (ref "ADC_2") (pin "1") (pinfunction "CH0_1") (pintype "input"))
      (node (ref "ANALOG_BANK2") (pin "8") (pinfunction "8_8") (pintype "passive"))
    )
    (net (code "81") (name "Net-(ADC_2-CH1)") (class "Default")
      (node (ref "ADC_2") (pin "2") (pinfunction "CH1_2") (pintype "input"))
      (node (ref "ANALOG_BANK2") (pin "7") (pinfunction "7_7") (pintype "passive"))
    )
    (net (code "82") (name "Net-(ADC_2-CH2)") (class "Default")
      (node (ref "ADC_2") (pin "3") (pinfunction "CH2_3") (pintype "input"))
      (node (ref "ANALOG_BANK2") (pin "6") (pinfunction "6_6") (pintype "passive"))
    )
    (net (code "83") (name "Net-(ADC_2-CH3)") (class "Default")
      (node (ref "ADC_2") (pin "4") (pinfunction "CH3_4") (pintype "input"))
      (node (ref "ANALOG_BANK2") (pin "5") (pinfunction "5_5") (pintype "passive"))
    )
    (net (code "84") (name "Net-(ADC_2-CH4)") (class "Default")
      (node (ref "ADC_2") (pin "5") (pinfunction "CH4_5") (pintype "input"))
      (node (ref "ANALOG_BANK2") (pin "4") (pinfunction "4_4") (pintype "passive"))
    )
    (net (code "85") (name "Net-(ADC_2-CH5)") (class "Default")
      (node (ref "ADC_2") (pin "6") (pinfunction "CH5_6") (pintype "input"))
      (node (ref "ANALOG_BANK2") (pin "3") (pinfunction "3_3") (pintype "passive"))
    )
    (net (code "86") (name "Net-(ADC_2-CH6)") (class "Default")
      (node (ref "ADC_2") (pin "7") (pinfunction "CH6_7") (pintype "input"))
      (node (ref "ANALOG_BANK2") (pin "2") (pinfunction "2_2") (pintype "passive"))
    )
    (net (code "87") (name "Net-(ADC_2-CH7)") (class "Default")
      (node (ref "ADC_2") (pin "8") (pinfunction "CH7_8") (pintype "input"))
      (node (ref "ANALOG_BANK2") (pin "1") (pinfunction "1_1") (pintype "passive"))
    )
    (net (code "88") (name "Net-(ADC_2-~{CS{slash}SHDN})") (class "Default")
      (node (ref "ADC_2") (pin "10") (pinfunction "~{CS/SHDN}_10") (pintype "input"))
      (node (ref "CS_CONT") (pin "24") (pinfunction "GPA3_24") (pintype "bidirectional"))
    )
    (net (code "89") (name "Net-(ADC_3-CH0)") (class "Default")
      (node (ref "ADC_3") (pin "1") (pinfunction "CH0_1") (pintype "input"))
      (node (ref "ANALOG_BANK3") (pin "8") (pinfunction "8_8") (pintype "passive"))
    )
    (net (code "90") (name "Net-(ADC_3-CH1)") (class "Default")
      (node (ref "ADC_3") (pin "2") (pinfunction "CH1_2") (pintype "input"))
      (node (ref "ANALOG_BANK3") (pin "7") (pinfunction "7_7") (pintype "passive"))
    )
    (net (code "91") (name "Net-(ADC_3-CH2)") (class "Default")
      (node (ref "ADC_3") (pin "3") (pinfunction "CH2_3") (pintype "input"))
      (node (ref "ANALOG_BANK3") (pin "6") (pinfunction "6_6") (pintype "passive"))
    )
    (net (code "92") (name "Net-(ADC_3-CH3)") (class "Default")
      (node (ref "ADC_3") (pin "4") (pinfunction "CH3_4") (pintype "input"))
      (node (ref "ANALOG_BANK3") (pin "5") (pinfunction "5_5") (pintype "passive"))
    )
    (net (code "93") (name "Net-(ADC_3-CH4)") (class "Default")
      (node (ref "ADC_3") (pin "5") (pinfunction "CH4_5") (pintype "input"))
      (node (ref "ANALOG_BANK3") (pin "4") (pinfunction "4_4") (pintype "passive"))
    )
    (net (code "94") (name "Net-(ADC_3-CH5)") (class "Default")
      (node (ref "ADC_3") (pin "6") (pinfunction "CH5_6") (pintype "input"))
      (node (ref "ANALOG_BANK3") (pin "3") (pinfunction "3_3") (pintype "passive"))
    )
    (net (code "95") (name "Net-(ADC_3-CH6)") (class "Default")
      (node (ref "ADC_3") (pin "7") (pinfunction "CH6_7") (pintype "input"))
      (node (ref "ANALOG_BANK3") (pin "2") (pinfunction "2_2") (pintype "passive"))
    )
    (net (code "96") (name "Net-(ADC_3-CH7)") (class "Default")
      (node (ref "ADC_3") (pin "8") (pinfunction "CH7_8") (pintype "input"))
      (node (ref "ANALOG_BANK3") (pin "1") (pinfunction "1_1") (pintype "passive"))
    )
    (net (code "97") (name "Net-(ADC_3-~{CS{slash}SHDN})") (class "Default")
      (node (ref "ADC_3") (pin "10") (pinfunction "~{CS/SHDN}_10") (pintype "input"))
      (node (ref "CS_CONT") (pin "25") (pinfunction "GPA4_25") (pintype "bidirectional"))
    )
    (net (code "98") (name "Net-(GPIO_0-GPA0)") (class "Default")
      (node (ref "GPIO_0") (pin "21") (pinfunction "GPA0_21") (pintype "bidirectional"))
      (node (ref "GPIO_BANK0") (pin "1") (pinfunction "1_1") (pintype "passive"))
    )
    (net (code "99") (name "Net-(GPIO_0-GPA1)") (class "Default")
      (node (ref "GPIO_0") (pin "22") (pinfunction "GPA1_22") (pintype "bidirectional"))
      (node (ref "GPIO_BANK0") (pin "2") (pinfunction "2_2") (pintype "passive"))
    )
    (net (code "100") (name "Net-(GPIO_0-GPA2)") (class "Default")
      (node (ref "GPIO_0") (pin "23") (pinfunction "GPA2_23") (pintype "bidirectional"))
      (node (ref "GPIO_BANK0") (pin "3") (pinfunction "3_3") (pintype "passive"))
    )
    (net (code "101") (name "Net-(GPIO_0-GPA3)") (class "Default")
      (node (ref "GPIO_0") (pin "24") (pinfunction "GPA3_24") (pintype "bidirectional"))
      (node (ref "GPIO_BANK0") (pin "4") (pinfunction "4_4") (pintype "passive"))
    )
    (net (code "102") (name "Net-(GPIO_0-GPA4)") (class "Default")
      (node (ref "GPIO_0") (pin "25") (pinfunction "GPA4_25") (pintype "bidirectional"))
      (node (ref "GPIO_BANK0") (pin "5") (pinfunction "5_5") (pintype "passive"))
    )
    (net (code "103") (name "Net-(GPIO_0-GPA5)") (class "Default")
      (node (ref "GPIO_0") (pin "26") (pinfunction "GPA5_26") (pintype "bidirectional"))
      (node (ref "GPIO_BANK0") (pin "6") (pinfunction "6_6") (pintype "passive"))
    )
    (net (code "104") (name "Net-(GPIO_0-GPA6)") (class "Default")
      (node (ref "GPIO_0") (pin "27") (pinfunction "GPA6_27") (pintype "bidirectional"))
      (node (ref "GPIO_BANK0") (pin "7") (pinfunction "7_7") (pintype "passive"))
    )
    (net (code "105") (name "Net-(GPIO_0-GPA7)") (class "Default")
      (node (ref "GPIO_0") (pin "28") (pinfunction "GPA7_28") (pintype "bidirectional"))
      (node (ref "GPIO_BANK0") (pin "8") (pinfunction "8_8") (pintype "passive"))
    )
    (net (code "106") (name "Net-(GPIO_0-GPB0)") (class "Default")
      (node (ref "GPIO_0") (pin "1") (pinfunction "GPB0_1") (pintype "bidirectional"))
      (node (ref "GPIO_BANK1") (pin "1") (pinfunction "1_1") (pintype "passive"))
    )
    (net (code "107") (name "Net-(GPIO_0-GPB1)") (class "Default")
      (node (ref "GPIO_0") (pin "2") (pinfunction "GPB1_2") (pintype "bidirectional"))
      (node (ref "GPIO_BANK1") (pin "2") (pinfunction "2_2") (pintype "passive"))
    )
    (net (code "108") (name "Net-(GPIO_0-GPB2)") (class "Default")
      (node (ref "GPIO_0") (pin "3") (pinfunction "GPB2_3") (pintype "bidirectional"))
      (node (ref "GPIO_BANK1") (pin "3") (pinfunction "3_3") (pintype "passive"))
    )
    (net (code "109") (name "Net-(GPIO_0-GPB3)") (class "Default")
      (node (ref "GPIO_0") (pin "4") (pinfunction "GPB3_4") (pintype "bidirectional"))
      (node (ref "GPIO_BANK1") (pin "4") (pinfunction "4_4") (pintype "passive"))
    )
    (net (code "110") (name "Net-(GPIO_0-GPB4)") (class "Default")
      (node (ref "GPIO_0") (pin "5") (pinfunction "GPB4_5") (pintype "bidirectional"))
      (node (ref "GPIO_BANK1") (pin "5") (pinfunction "5_5") (pintype "passive"))
    )
    (net (code "111") (name "Net-(GPIO_0-GPB5)") (class "Default")
      (node (ref "GPIO_0") (pin "6") (pinfunction "GPB5_6") (pintype "bidirectional"))
      (node (ref "GPIO_BANK1") (pin "6") (pinfunction "6_6") (pintype "passive"))
    )
    (net (code "112") (name "Net-(GPIO_0-GPB6)") (class "Default")
      (node (ref "GPIO_0") (pin "7") (pinfunction "GPB6_7") (pintype "bidirectional"))
      (node (ref "GPIO_BANK1") (pin "7") (pinfunction "7_7") (pintype "passive"))
    )
    (net (code "113") (name "Net-(GPIO_0-GPB7)") (class "Default")
      (node (ref "GPIO_0") (pin "8") (pinfunction "GPB7_8") (pintype "bidirectional"))
      (node (ref "GPIO_BANK1") (pin "8") (pinfunction "8_8") (pintype "passive"))
    )
    (net (code "114") (name "Net-(GPIO_0-VSS)") (class "Default")
      (node (ref "GPIO_0") (pin "10") (pinfunction "VSS_10") (pintype "power_in"))
      (node (ref "GPIO_1") (pin "10") (pinfunction "VSS_10") (pintype "power_in"))
    )
    (net (code "115") (name "Net-(GPIO_1-GPA0)") (class "Default")
      (node (ref "GPIO_1") (pin "21") (pinfunction "GPA0_21") (pintype "bidirectional"))
      (node (ref "GPIO_BANK2") (pin "1") (pinfunction "1_1") (pintype "passive"))
    )
    (net (code "116") (name "Net-(GPIO_1-GPA1)") (class "Default")
      (node (ref "GPIO_1") (pin "22") (pinfunction "GPA1_22") (pintype "bidirectional"))
      (node (ref "GPIO_BANK2") (pin "2") (pinfunction "2_2") (pintype "passive"))
    )
    (net (code "117") (name "Net-(GPIO_1-GPA2)") (class "Default")
      (node (ref "GPIO_1") (pin "23") (pinfunction "GPA2_23") (pintype "bidirectional"))
      (node (ref "GPIO_BANK2") (pin "3") (pinfunction "3_3") (pintype "passive"))
    )
    (net (code "118") (name "Net-(GPIO_1-GPA3)") (class "Default")
      (node (ref "GPIO_1") (pin "24") (pinfunction "GPA3_24") (pintype "bidirectional"))
      (node (ref "GPIO_BANK2") (pin "4") (pinfunction "4_4") (pintype "passive"))
    )
    (net (code "119") (name "Net-(GPIO_1-GPA4)") (class "Default")
      (node (ref "GPIO_1") (pin "25") (pinfunction "GPA4_25") (pintype "bidirectional"))
      (node (ref "GPIO_BANK2") (pin "5") (pinfunction "5_5") (pintype "passive"))
    )
    (net (code "120") (name "Net-(GPIO_1-GPA5)") (class "Default")
      (node (ref "GPIO_1") (pin "26") (pinfunction "GPA5_26") (pintype "bidirectional"))
      (node (ref "GPIO_BANK2") (pin "6") (pinfunction "6_6") (pintype "passive"))
    )
    (net (code "121") (name "Net-(GPIO_1-GPA6)") (class "Default")
      (node (ref "GPIO_1") (pin "27") (pinfunction "GPA6_27") (pintype "bidirectional"))
      (node (ref "GPIO_BANK2") (pin "7") (pinfunction "7_7") (pintype "passive"))
    )
    (net (code "122") (name "Net-(GPIO_1-GPA7)") (class "Default")
      (node (ref "GPIO_1") (pin "28") (pinfunction "GPA7_28") (pintype "bidirectional"))
      (node (ref "GPIO_BANK2") (pin "8") (pinfunction "8_8") (pintype "passive"))
    )
    (net (code "123") (name "Net-(GPIO_1-GPB0)") (class "Default")
      (node (ref "GPIO_1") (pin "1") (pinfunction "GPB0_1") (pintype "bidirectional"))
      (node (ref "GPIO_BANK3") (pin "1") (pinfunction "1_1") (pintype "passive"))
    )
    (net (code "124") (name "Net-(GPIO_1-GPB1)") (class "Default")
      (node (ref "GPIO_1") (pin "2") (pinfunction "GPB1_2") (pintype "bidirectional"))
      (node (ref "GPIO_BANK3") (pin "2") (pinfunction "2_2") (pintype "passive"))
    )
    (net (code "125") (name "Net-(GPIO_1-GPB2)") (class "Default")
      (node (ref "GPIO_1") (pin "3") (pinfunction "GPB2_3") (pintype "bidirectional"))
      (node (ref "GPIO_BANK3") (pin "3") (pinfunction "3_3") (pintype "passive"))
    )
    (net (code "126") (name "Net-(GPIO_1-GPB3)") (class "Default")
      (node (ref "GPIO_1") (pin "4") (pinfunction "GPB3_4") (pintype "bidirectional"))
      (node (ref "GPIO_BANK3") (pin "4") (pinfunction "4_4") (pintype "passive"))
    )
    (net (code "127") (name "Net-(GPIO_1-GPB4)") (class "Default")
      (node (ref "GPIO_1") (pin "5") (pinfunction "GPB4_5") (pintype "bidirectional"))
      (node (ref "GPIO_BANK3") (pin "5") (pinfunction "5_5") (pintype "passive"))
    )
    (net (code "128") (name "Net-(GPIO_1-GPB5)") (class "Default")
      (node (ref "GPIO_1") (pin "6") (pinfunction "GPB5_6") (pintype "bidirectional"))
      (node (ref "GPIO_BANK3") (pin "6") (pinfunction "6_6") (pintype "passive"))
    )
    (net (code "129") (name "Net-(GPIO_1-GPB6)") (class "Default")
      (node (ref "GPIO_1") (pin "7") (pinfunction "GPB6_7") (pintype "bidirectional"))
      (node (ref "GPIO_BANK3") (pin "7") (pinfunction "7_7") (pintype "passive"))
    )
    (net (code "130") (name "Net-(GPIO_1-GPB7)") (class "Default")
      (node (ref "GPIO_1") (pin "8") (pinfunction "GPB7_8") (pintype "bidirectional"))
      (node (ref "GPIO_BANK3") (pin "8") (pinfunction "8_8") (pintype "passive"))
    )
    (net (code "131") (name "Net-(LED1-PadA)") (class "Default")
      (node (ref "LED1") (pin "A") (pinfunction "A_A") (pintype "passive"))
      (node (ref "R1") (pin "1") (pinfunction "1_1") (pintype "passive"))
    )
    (net (code "132") (name "Net-(LED2-PadA)") (class "Default")
      (node (ref "LED2") (pin "A") (pinfunction "A_A") (pintype "passive"))
      (node (ref "R2") (pin "1") (pinfunction "1_1") (pintype "passive"))
    )
    (net (code "133") (name "Net-(LED3-PadA)") (class "Default")
      (node (ref "LED3") (pin "A") (pinfunction "A_A") (pintype "passive"))
      (node (ref "R3") (pin "1") (pinfunction "1_1") (pintype "passive"))
    )
    (net (code "134") (name "Net-(SHIFT_CON-PB0)") (class "Default")
      (node (ref "R1") (pin "2") (pinfunction "2_2") (pintype "passive"))
      (node (ref "SHIFT_CON") (pin "14") (pinfunction "PB0_14") (pintype "bidirectional"))
    )
    (net (code "135") (name "Net-(SHIFT_CON-PB1)") (class "Default")
      (node (ref "R2") (pin "2") (pinfunction "2_2") (pintype "passive"))
      (node (ref "SHIFT_CON") (pin "15") (pinfunction "PB1_15") (pintype "bidirectional"))
    )
    (net (code "136") (name "Net-(SHIFT_CON-PB2)") (class "Default")
      (node (ref "R3") (pin "2") (pinfunction "2_2") (pintype "passive"))
      (node (ref "SHIFT_CON") (pin "16") (pinfunction "PB2_16") (pintype "bidirectional"))
    )
    (net (code "137") (name "Net-(SHIFT_INA-A)") (class "Default")
      (node (ref "DIP_ARRAY") (pin "8") (pinfunction "8_8") (pintype "passive"))
      (node (ref "RN1") (pin "9") (pinfunction "9_9") (pintype "passive"))
      (node (ref "SHIFT_IN") (pin "11") (pinfunction "A_11") (pintype "input"))
    )
    (net (code "138") (name "Net-(SHIFT_INA-B)") (class "Default")
      (node (ref "DIP_ARRAY") (pin "7") (pinfunction "7_7") (pintype "passive"))
      (node (ref "RN1") (pin "8") (pinfunction "8_8") (pintype "passive"))
      (node (ref "SHIFT_IN") (pin "12") (pinfunction "B_12") (pintype "input"))
    )
    (net (code "139") (name "Net-(SHIFT_INA-C)") (class "Default")
      (node (ref "DIP_ARRAY") (pin "6") (pinfunction "6_6") (pintype "passive"))
      (node (ref "RN1") (pin "7") (pinfunction "7_7") (pintype "passive"))
      (node (ref "SHIFT_IN") (pin "13") (pinfunction "C_13") (pintype "input"))
    )
    (net (code "140") (name "Net-(SHIFT_INA-D)") (class "Default")
      (node (ref "DIP_ARRAY") (pin "5") (pinfunction "5_5") (pintype "passive"))
      (node (ref "RN1") (pin "6") (pinfunction "6_6") (pintype "passive"))
      (node (ref "SHIFT_IN") (pin "14") (pinfunction "D_14") (pintype "input"))
    )
    (net (code "141") (name "Net-(SHIFT_INA-E)") (class "Default")
      (node (ref "DIP_ARRAY") (pin "4") (pinfunction "4_4") (pintype "passive"))
      (node (ref "RN1") (pin "5") (pinfunction "5_5") (pintype "passive"))
      (node (ref "SHIFT_IN") (pin "3") (pinfunction "E_3") (pintype "input"))
    )
    (net (code "142") (name "Net-(SHIFT_INA-F)") (class "Default")
      (node (ref "DIP_ARRAY") (pin "3") (pinfunction "3_3") (pintype "passive"))
      (node (ref "RN1") (pin "4") (pinfunction "4_4") (pintype "passive"))
      (node (ref "SHIFT_IN") (pin "4") (pinfunction "F_4") (pintype "input"))
    )
    (net (code "143") (name "Net-(SHIFT_INA-G)") (class "Default")
      (node (ref "DIP_ARRAY") (pin "2") (pinfunction "2_2") (pintype "passive"))
      (node (ref "RN1") (pin "3") (pinfunction "3_3") (pintype "passive"))
      (node (ref "SHIFT_IN") (pin "5") (pinfunction "G_5") (pintype "input"))
    )
    (net (code "144") (name "Net-(SHIFT_INA-H)") (class "Default")
      (node (ref "DIP_ARRAY") (pin "1") (pinfunction "1_1") (pintype "passive"))
      (node (ref "RN1") (pin "2") (pinfunction "2_2") (pintype "passive"))
      (node (ref "SHIFT_IN") (pin "6") (pinfunction "H_6") (pintype "input"))
    )
    (net (code "145") (name "unconnected-(CS_CONT-GPB5-Pad6)") (class "Default")
      (node (ref "CS_CONT") (pin "6") (pinfunction "GPB5_6") (pintype "bidirectional"))
    )
    (net (code "146") (name "unconnected-(CS_CONT-GPB6-Pad7)") (class "Default")
      (node (ref "CS_CONT") (pin "7") (pinfunction "GPB6_7") (pintype "bidirectional"))
    )
    (net (code "147") (name "unconnected-(CS_CONT-GPB7-Pad8)") (class "Default")
      (node (ref "CS_CONT") (pin "8") (pinfunction "GPB7_8") (pintype "bidirectional"))
    )
    (net (code "148") (name "unconnected-(CS_CONT-INTA-Pad20)") (class "Default")
      (node (ref "CS_CONT") (pin "20") (pinfunction "INTA_20") (pintype "output"))
    )
    (net (code "149") (name "unconnected-(CS_CONT-INTB-Pad19)") (class "Default")
      (node (ref "CS_CONT") (pin "19") (pinfunction "INTB_19") (pintype "output"))
    )
    (net (code "150") (name "unconnected-(EXT_I2C-Pad4)") (class "Default")
      (node (ref "EXT_I2C") (pin "4") (pinfunction "4_4") (pintype "passive"))
    )
    (net (code "151") (name "unconnected-(EXT_I2C-Pad6)") (class "Default")
      (node (ref "EXT_I2C") (pin "6") (pinfunction "6_6") (pintype "passive"))
    )
    (net (code "152") (name "unconnected-(EXT_I2C-Pad7)") (class "Default")
      (node (ref "EXT_I2C") (pin "7") (pinfunction "7_7") (pintype "passive"))
    )
    (net (code "153") (name "unconnected-(EXT_I2C-Pad8)") (class "Default")
      (node (ref "EXT_I2C") (pin "8") (pinfunction "8_8") (pintype "passive"))
    )
    (net (code "154") (name "unconnected-(EXT_I2C-Pad9)") (class "Default")
      (node (ref "EXT_I2C") (pin "9") (pinfunction "9_9") (pintype "passive"))
    )
    (net (code "155") (name "unconnected-(EXT_SER-Pad6)") (class "Default")
      (node (ref "EXT_SER") (pin "6") (pinfunction "6_6") (pintype "passive"))
    )
    (net (code "156") (name "unconnected-(EXT_SER-Pad7)") (class "Default")
      (node (ref "EXT_SER") (pin "7") (pinfunction "7_7") (pintype "passive"))
    )
    (net (code "157") (name "unconnected-(EXT_SER-Pad8)") (class "Default")
      (node (ref "EXT_SER") (pin "8") (pinfunction "8_8") (pintype "passive"))
    )
    (net (code "158") (name "unconnected-(EXT_SER-Pad9)") (class "Default")
      (node (ref "EXT_SER") (pin "9") (pinfunction "9_9") (pintype "passive"))
    )
    (net (code "159") (name "unconnected-(GPIO_0-INTA-Pad20)") (class "Default")
      (node (ref "GPIO_0") (pin "20") (pinfunction "INTA_20") (pintype "output"))
    )
    (net (code "160") (name "unconnected-(GPIO_0-INTB-Pad19)") (class "Default")
      (node (ref "GPIO_0") (pin "19") (pinfunction "INTB_19") (pintype "output"))
    )
    (net (code "161") (name "unconnected-(GPIO_1-INTA-Pad20)") (class "Default")
      (node (ref "GPIO_1") (pin "20") (pinfunction "INTA_20") (pintype "output"))
    )
    (net (code "162") (name "unconnected-(GPIO_1-INTB-Pad19)") (class "Default")
      (node (ref "GPIO_1") (pin "19") (pinfunction "INTB_19") (pintype "output"))
    )
    (net (code "163") (name "unconnected-(LOGIC_SHIFT-HV_TXO_1-PadP$12)") (class "Default")
      (node (ref "LOGIC_SHIFT") (pin "P$12") (pinfunction "HV_TXO_1_P$12") (pintype "bidirectional"))
    )
    (net (code "164") (name "unconnected-(LOGIC_SHIFT-LV_RXO_1-PadP$2)") (class "Default")
      (node (ref "LOGIC_SHIFT") (pin "P$2") (pinfunction "LV_RXO_1_P$2") (pintype "bidirectional"))
    )
    (net (code "165") (name "unconnected-(SHIFT_CON-PB3-Pad17)") (class "Default")
      (node (ref "SHIFT_CON") (pin "17") (pinfunction "PB3_17") (pintype "bidirectional"))
    )
    (net (code "166") (name "unconnected-(SHIFT_CON-PB4-Pad18)") (class "Default")
      (node (ref "SHIFT_CON") (pin "18") (pinfunction "PB4_18") (pintype "bidirectional"))
    )
    (net (code "167") (name "unconnected-(SHIFT_CON-PB5-Pad19)") (class "Default")
      (node (ref "SHIFT_CON") (pin "19") (pinfunction "PB5_19") (pintype "bidirectional"))
    )
    (net (code "168") (name "unconnected-(SHIFT_CON-PD7-Pad13)") (class "Default")
      (node (ref "SHIFT_CON") (pin "13") (pinfunction "PD7_13") (pintype "bidirectional"))
    )
    (net (code "169") (name "unconnected-(SHIFT_INA-~{QH}-Pad7)") (class "Default")
      (node (ref "SHIFT_IN") (pin "7") (pinfunction "~{QH}_7") (pintype "output"))
    )
  )
)
